# bluz_jlink_shield_v1_revC.net
KiCad netlist of a schematic drawn in EAGLE
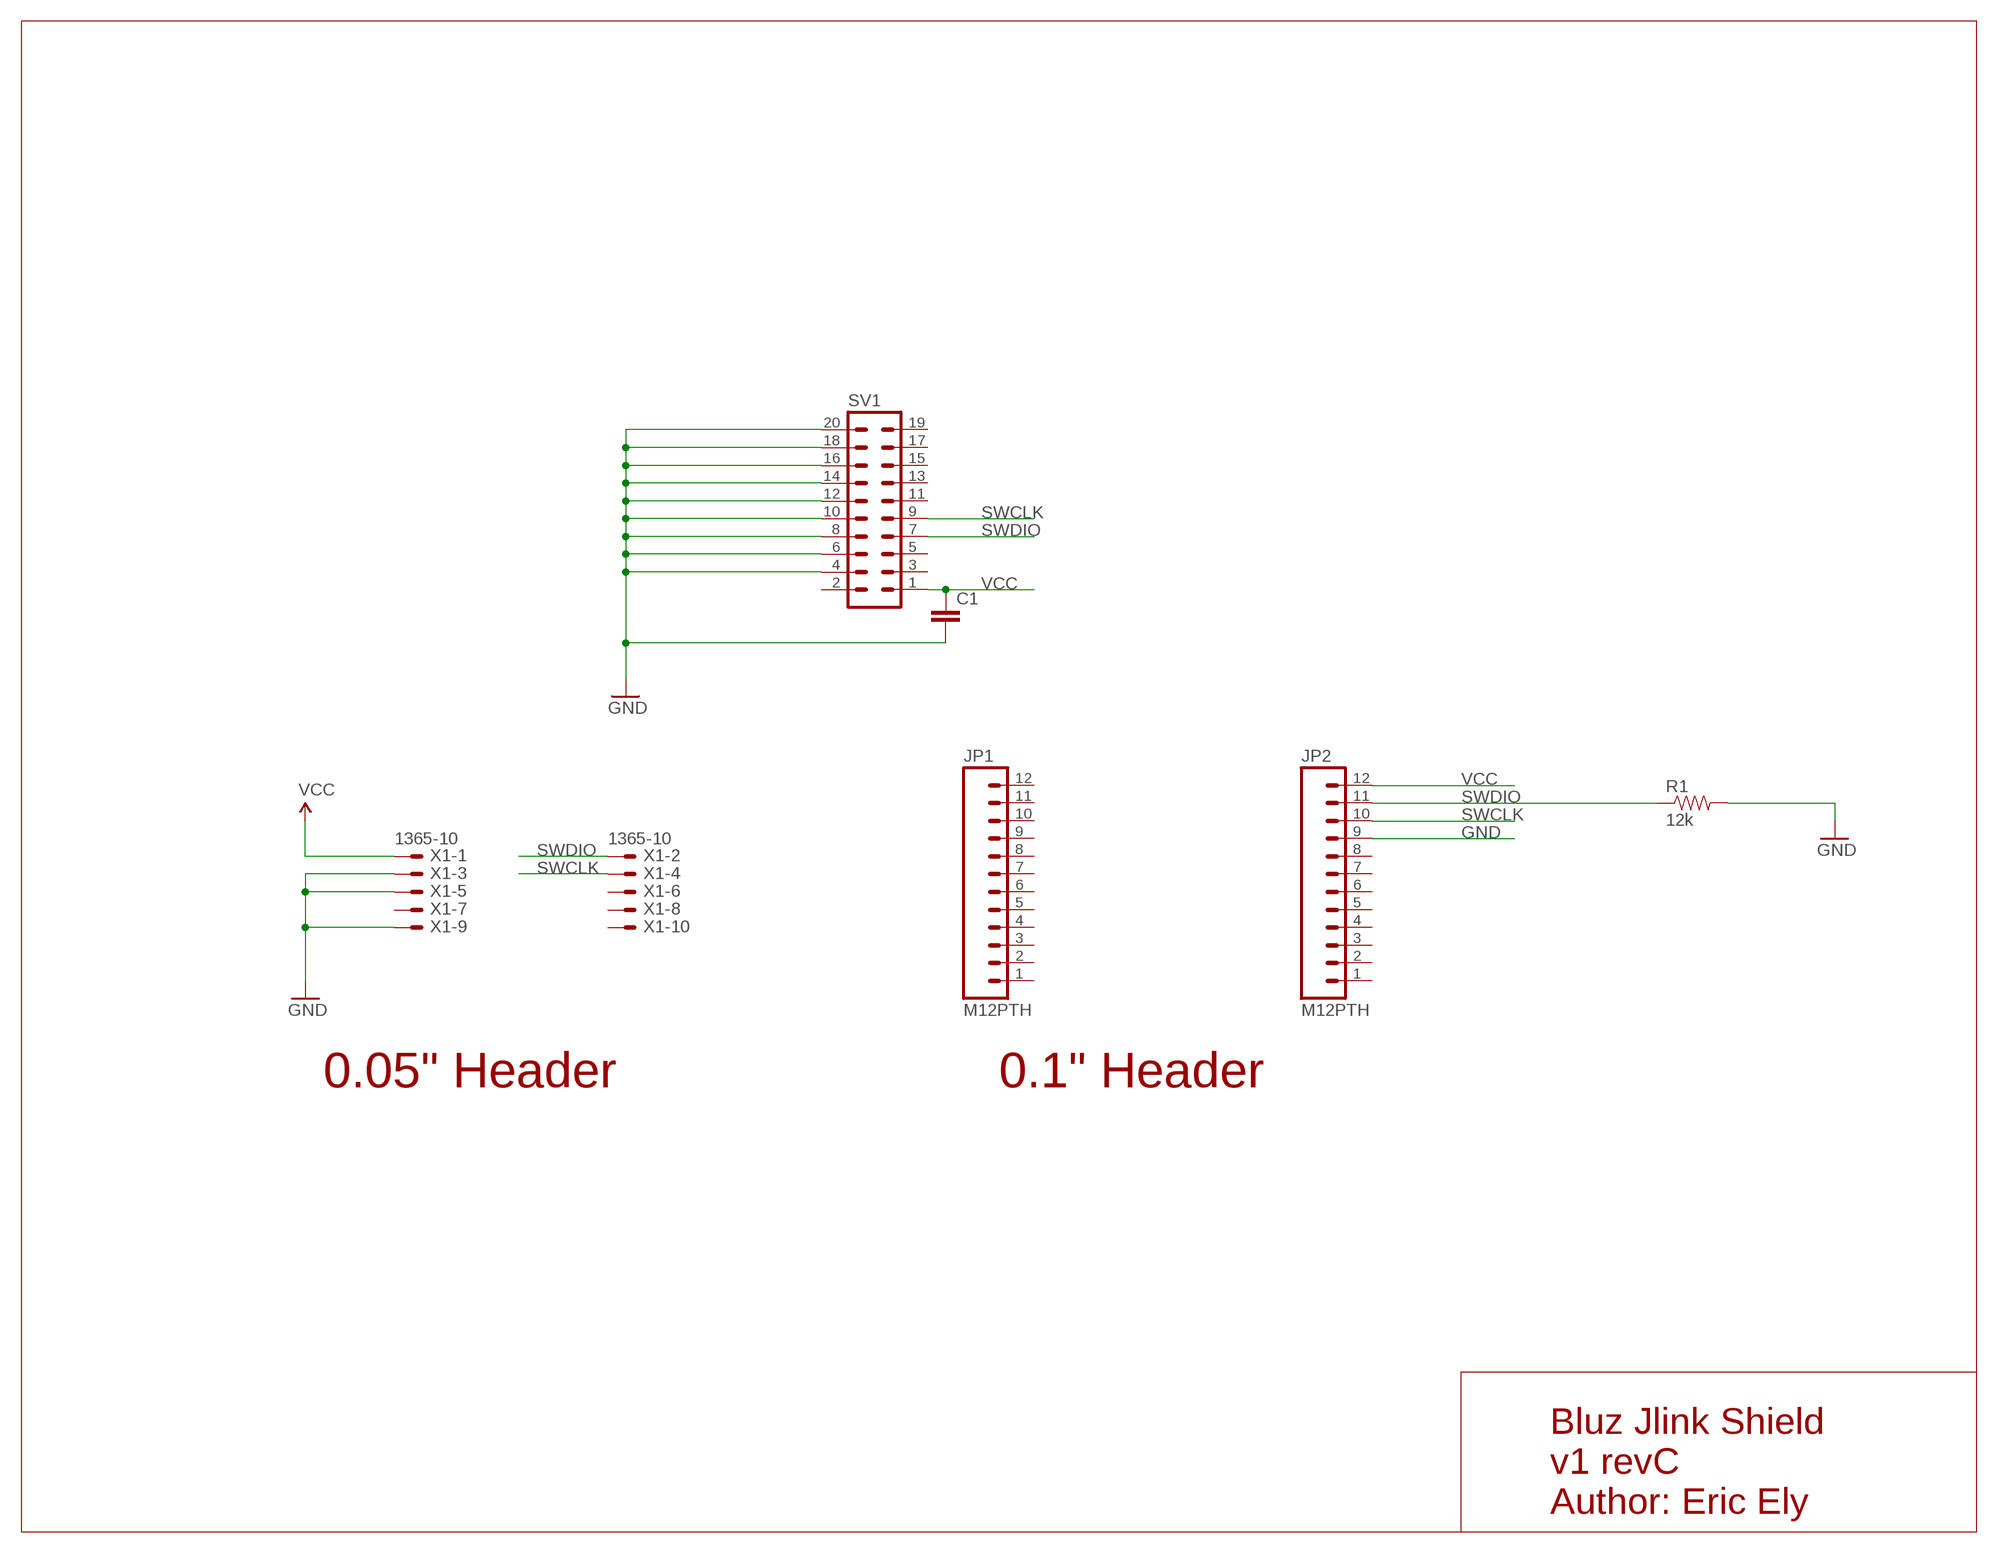
[diagram p0: schematic, sheet 1]

(export (version "E")
  (design (tool "Eeschema 10.0.6"))
  (components
    (comp (ref "C1")
      (value "CAP0603-CAP")
      (footprint "eagle-import:0603-CAP")
      (libsource (lib "eagle-import") (part "CAP0603-CAP"))
    )
    (comp (ref "JP1")
      (value "M12PTH")
      (footprint "eagle-import:1X12")
      (libsource (lib "eagle-import") (part "M12PTH"))
    )
    (comp (ref "JP2")
      (value "M12PTH")
      (footprint "eagle-import:1X12")
      (libsource (lib "eagle-import") (part "M12PTH"))
    )
    (comp (ref "R1")
      (value "12k")
      (footprint "eagle-import:0603-RES")
      (libsource (lib "eagle-import") (part "RESISTOR0603"))
    )
    (comp (ref "SV1")
      (value "ML20")
      (footprint "eagle-import:ML20")
      (libsource (lib "eagle-import") (part "ML20"))
    )
    (comp (ref "X1")
      (value "1365-10")
      (footprint "eagle-import:1365-10")
      (libsource (lib "eagle-import") (part "1365-10"))
    )
  )
  (nets
    (net (code "1") (name "/SWCLK") (class "Default")
      (node (ref "JP2") (pin "10") (pinfunction "10_10") (pintype "passive"))
      (node (ref "SV1") (pin "9") (pinfunction "9_9") (pintype "passive"))
      (node (ref "X1") (pin "4") (pinfunction "S_4") (pintype "passive"))
    )
    (net (code "2") (name "/SWDIO") (class "Default")
      (node (ref "JP2") (pin "11") (pinfunction "11_11") (pintype "passive"))
      (node (ref "R1") (pin "1") (pinfunction "1_1") (pintype "passive"))
      (node (ref "SV1") (pin "7") (pinfunction "7_7") (pintype "passive"))
      (node (ref "X1") (pin "2") (pinfunction "S_2") (pintype "passive"))
    )
    (net (code "3") (name "GND") (class "Default")
      (node (ref "C1") (pin "2") (pinfunction "2_2") (pintype "passive"))
      (node (ref "JP2") (pin "9") (pinfunction "9_9") (pintype "passive"))
      (node (ref "R1") (pin "2") (pinfunction "2_2") (pintype "passive"))
      (node (ref "SV1") (pin "10") (pinfunction "10_10") (pintype "passive"))
      (node (ref "SV1") (pin "12") (pinfunction "12_12") (pintype "passive"))
      (node (ref "SV1") (pin "14") (pinfunction "14_14") (pintype "passive"))
      (node (ref "SV1") (pin "16") (pinfunction "16_16") (pintype "passive"))
      (node (ref "SV1") (pin "18") (pinfunction "18_18") (pintype "passive"))
      (node (ref "SV1") (pin "20") (pinfunction "20_20") (pintype "passive"))
      (node (ref "SV1") (pin "4") (pinfunction "4_4") (pintype "passive"))
      (node (ref "SV1") (pin "6") (pinfunction "6_6") (pintype "passive"))
      (node (ref "SV1") (pin "8") (pinfunction "8_8") (pintype "passive"))
      (node (ref "X1") (pin "3") (pinfunction "S_3") (pintype "passive"))
      (node (ref "X1") (pin "5") (pinfunction "S_5") (pintype "passive"))
      (node (ref "X1") (pin "9") (pinfunction "S_9") (pintype "passive"))
    )
    (net (code "4") (name "VCC") (class "Default")
      (node (ref "C1") (pin "1") (pinfunction "1_1") (pintype "passive"))
      (node (ref "JP2") (pin "12") (pinfunction "12_12") (pintype "passive"))
      (node (ref "SV1") (pin "1") (pinfunction "1_1") (pintype "passive"))
      (node (ref "X1") (pin "1") (pinfunction "S_1") (pintype "passive"))
    )
    (net (code "5") (name "unconnected-(JP1-Pad1)") (class "Default")
      (node (ref "JP1") (pin "1") (pinfunction "1_1") (pintype "passive"))
    )
    (net (code "6") (name "unconnected-(JP1-Pad2)") (class "Default")
      (node (ref "JP1") (pin "2") (pinfunction "2_2") (pintype "passive"))
    )
    (net (code "7") (name "unconnected-(JP1-Pad3)") (class "Default")
      (node (ref "JP1") (pin "3") (pinfunction "3_3") (pintype "passive"))
    )
    (net (code "8") (name "unconnected-(JP1-Pad4)") (class "Default")
      (node (ref "JP1") (pin "4") (pinfunction "4_4") (pintype "passive"))
    )
    (net (code "9") (name "unconnected-(JP1-Pad5)") (class "Default")
      (node (ref "JP1") (pin "5") (pinfunction "5_5") (pintype "passive"))
    )
    (net (code "10") (name "unconnected-(JP1-Pad6)") (class "Default")
      (node (ref "JP1") (pin "6") (pinfunction "6_6") (pintype "passive"))
    )
    (net (code "11") (name "unconnected-(JP1-Pad7)") (class "Default")
      (node (ref "JP1") (pin "7") (pinfunction "7_7") (pintype "passive"))
    )
    (net (code "12") (name "unconnected-(JP1-Pad8)") (class "Default")
      (node (ref "JP1") (pin "8") (pinfunction "8_8") (pintype "passive"))
    )
    (net (code "13") (name "unconnected-(JP1-Pad9)") (class "Default")
      (node (ref "JP1") (pin "9") (pinfunction "9_9") (pintype "passive"))
    )
    (net (code "14") (name "unconnected-(JP1-Pad10)") (class "Default")
      (node (ref "JP1") (pin "10") (pinfunction "10_10") (pintype "passive"))
    )
    (net (code "15") (name "unconnected-(JP1-Pad11)") (class "Default")
      (node (ref "JP1") (pin "11") (pinfunction "11_11") (pintype "passive"))
    )
    (net (code "16") (name "unconnected-(JP1-Pad12)") (class "Default")
      (node (ref "JP1") (pin "12") (pinfunction "12_12") (pintype "passive"))
    )
    (net (code "17") (name "unconnected-(JP2-Pad1)") (class "Default")
      (node (ref "JP2") (pin "1") (pinfunction "1_1") (pintype "passive"))
    )
    (net (code "18") (name "unconnected-(JP2-Pad2)") (class "Default")
      (node (ref "JP2") (pin "2") (pinfunction "2_2") (pintype "passive"))
    )
    (net (code "19") (name "unconnected-(JP2-Pad3)") (class "Default")
      (node (ref "JP2") (pin "3") (pinfunction "3_3") (pintype "passive"))
    )
    (net (code "20") (name "unconnected-(JP2-Pad4)") (class "Default")
      (node (ref "JP2") (pin "4") (pinfunction "4_4") (pintype "passive"))
    )
    (net (code "21") (name "unconnected-(JP2-Pad5)") (class "Default")
      (node (ref "JP2") (pin "5") (pinfunction "5_5") (pintype "passive"))
    )
    (net (code "22") (name "unconnected-(JP2-Pad6)") (class "Default")
      (node (ref "JP2") (pin "6") (pinfunction "6_6") (pintype "passive"))
    )
    (net (code "23") (name "unconnected-(JP2-Pad7)") (class "Default")
      (node (ref "JP2") (pin "7") (pinfunction "7_7") (pintype "passive"))
    )
    (net (code "24") (name "unconnected-(JP2-Pad8)") (class "Default")
      (node (ref "JP2") (pin "8") (pinfunction "8_8") (pintype "passive"))
    )
    (net (code "25") (name "unconnected-(SV1-Pad2)") (class "Default")
      (node (ref "SV1") (pin "2") (pinfunction "2_2") (pintype "passive"))
    )
    (net (code "26") (name "unconnected-(SV1-Pad3)") (class "Default")
      (node (ref "SV1") (pin "3") (pinfunction "3_3") (pintype "passive"))
    )
    (net (code "27") (name "unconnected-(SV1-Pad5)") (class "Default")
      (node (ref "SV1") (pin "5") (pinfunction "5_5") (pintype "passive"))
    )
    (net (code "28") (name "unconnected-(SV1-Pad11)") (class "Default")
      (node (ref "SV1") (pin "11") (pinfunction "11_11") (pintype "passive"))
    )
    (net (code "29") (name "unconnected-(SV1-Pad13)") (class "Default")
      (node (ref "SV1") (pin "13") (pinfunction "13_13") (pintype "passive"))
    )
    (net (code "30") (name "unconnected-(SV1-Pad15)") (class "Default")
      (node (ref "SV1") (pin "15") (pinfunction "15_15") (pintype "passive"))
    )
    (net (code "31") (name "unconnected-(SV1-Pad17)") (class "Default")
      (node (ref "SV1") (pin "17") (pinfunction "17_17") (pintype "passive"))
    )
    (net (code "32") (name "unconnected-(SV1-Pad19)") (class "Default")
      (node (ref "SV1") (pin "19") (pinfunction "19_19") (pintype "passive"))
    )
    (net (code "33") (name "unconnected-(X1B-S-Pad10)") (class "Default")
      (node (ref "X1") (pin "10") (pinfunction "S_10") (pintype "passive"))
    )
    (net (code "34") (name "unconnected-(X1G-S-Pad6)") (class "Default")
      (node (ref "X1") (pin "6") (pinfunction "S_6") (pintype "passive"))
    )
    (net (code "35") (name "unconnected-(X1H-S-Pad7)") (class "Default")
      (node (ref "X1") (pin "7") (pinfunction "S_7") (pintype "passive"))
    )
    (net (code "36") (name "unconnected-(X1I-S-Pad8)") (class "Default")
      (node (ref "X1") (pin "8") (pinfunction "S_8") (pintype "passive"))
    )
  )
)
